# DAC_Block.net
KiCad netlist of a schematic drawn in Altium Designer
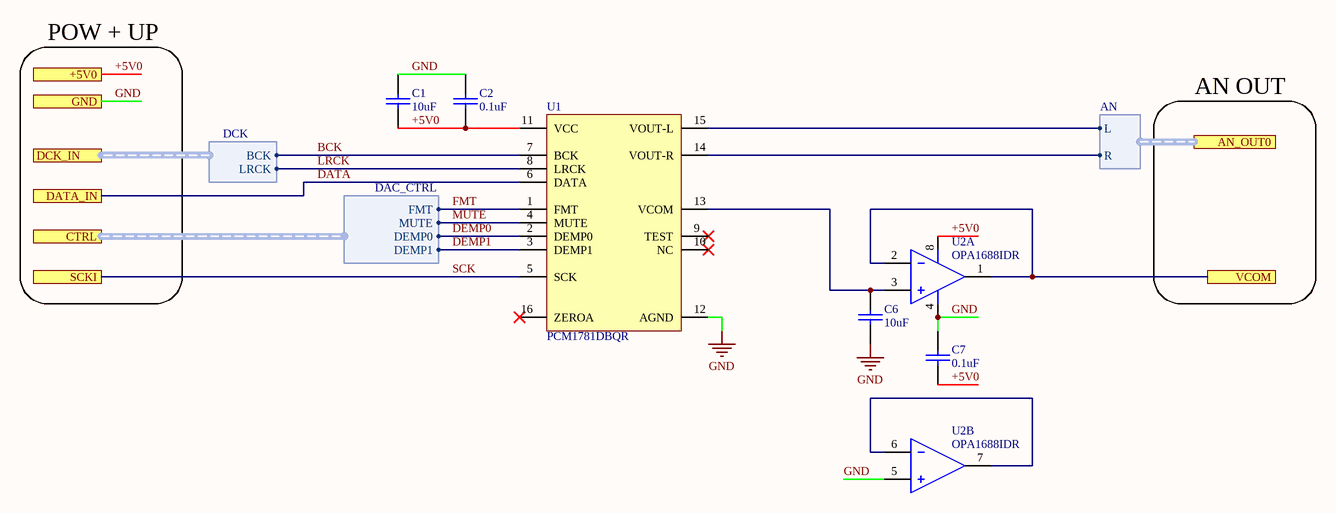
[diagram p0: DAC_Block.SchDoc]

(export (version "E")
  (design (tool "Eeschema 10.0.6"))
  (components
    (comp (ref "C1")
      (value "10uF")
      (footprint "0603-CAP-TDK")
      (fields (field (name "JLCPART") "C96446"))
      (libsource (lib "LIB2022 - Passives") (part "CAP-SMD"))
    )
    (comp (ref "C2")
      (value "0.1uF")
      (footprint "0402-CAP-TDK")
      (fields (field (name "JLCPART") "C307331"))
      (libsource (lib "LIB2022 - Passives") (part "CAP-SMD"))
    )
    (comp (ref "C6")
      (value "10uF")
      (footprint "0603-CAP-TDK")
      (fields (field (name "JLCPART") "C96446"))
      (libsource (lib "LIB2022 - Passives") (part "CAP-SMD"))
    )
    (comp (ref "C7")
      (value "0.1uF")
      (footprint "0402-CAP-TDK")
      (fields (field (name "JLCPART") "C307331"))
      (libsource (lib "LIB2022 - Passives") (part "CAP-SMD"))
    )
    (comp (ref "U1")
      (value "PCM1781DBQR")
      (footprint "TI-SSOP-16 - DBQ0016A")
      (description "DAC, Audio 24 b 192k DSP, I2S 16-SSOP")
      (fields (field (name "JLCPART") "C2667281"))
      (libsource (lib "LIB2022 - ICs") (part "PCM1781DBQR"))
    )
    (comp (ref "U2")
      (value "OPA1688IDR")
      (footprint "TI-SOIC-8")
      (description "Rail-To-Rail Amplifier 2 Circuit - 8-SOIC")
      (fields (field (name "JLCPART") "C206212"))
      (libsource (lib "LIB2022 - ICs") (part "OPA1688IDR"))
    )
  )
  (nets
    (net (code "4") (name "/+5V0") (class "Default")
      (node (ref "C1") (pin "2") (pinfunction "2_2") (pintype "passive"))
      (node (ref "C2") (pin "2") (pinfunction "2_2") (pintype "passive"))
      (node (ref "C7") (pin "1") (pinfunction "1_1") (pintype "passive"))
      (node (ref "U1") (pin "11") (pinfunction "VCC_11") (pintype "passive"))
      (node (ref "U2") (pin "8") (pinfunction "VDD_8") (pintype "power_in"))
    )
    (net (code "5") (name "/BCK") (class "Default")
      (node (ref "U1") (pin "7") (pinfunction "BCK_7") (pintype "passive"))
    )
    (net (code "6") (name "/DATA") (class "Default")
      (node (ref "U1") (pin "6") (pinfunction "DATA_6") (pintype "passive"))
    )
    (net (code "7") (name "/DEMP0") (class "Default")
      (node (ref "U1") (pin "2") (pinfunction "DEMP0_2") (pintype "passive"))
    )
    (net (code "8") (name "/DEMP1") (class "Default")
      (node (ref "U1") (pin "3") (pinfunction "DEMP1_3") (pintype "passive"))
    )
    (net (code "9") (name "/FMT") (class "Default")
      (node (ref "U1") (pin "1") (pinfunction "FMT_1") (pintype "passive"))
    )
    (net (code "10") (name "/L") (class "Default")
      (node (ref "U1") (pin "15") (pinfunction "VOUT-L_15") (pintype "passive"))
    )
    (net (code "11") (name "/LRCK") (class "Default")
      (node (ref "U1") (pin "8") (pinfunction "LRCK_8") (pintype "passive"))
    )
    (net (code "12") (name "/MUTE") (class "Default")
      (node (ref "U1") (pin "4") (pinfunction "MUTE_4") (pintype "passive"))
    )
    (net (code "13") (name "/R") (class "Default")
      (node (ref "U1") (pin "14") (pinfunction "VOUT-R_14") (pintype "passive"))
    )
    (net (code "14") (name "/SCK") (class "Default")
      (node (ref "U1") (pin "5") (pinfunction "SCK_5") (pintype "passive"))
    )
    (net (code "15") (name "/VCOM") (class "Default")
      (node (ref "U2") (pin "1") (pinfunction "1OUT_1") (pintype "passive"))
      (node (ref "U2") (pin "2") (pinfunction "1IN-_2") (pintype "passive"))
    )
    (net (code "19") (name "GND") (class "Default")
      (node (ref "C1") (pin "1") (pinfunction "1_1") (pintype "passive"))
      (node (ref "C2") (pin "1") (pinfunction "1_1") (pintype "passive"))
      (node (ref "C6") (pin "1") (pinfunction "1_1") (pintype "passive"))
      (node (ref "C7") (pin "2") (pinfunction "2_2") (pintype "passive"))
      (node (ref "U1") (pin "12") (pinfunction "AGND_12") (pintype "passive"))
      (node (ref "U2") (pin "4") (pinfunction "GND_4") (pintype "passive"))
      (node (ref "U2") (pin "5") (pinfunction "2IN+_5") (pintype "passive"))
    )
    (net (code "20") (name "Net-(U1-VCOM)") (class "Default")
      (node (ref "C6") (pin "2") (pinfunction "2_2") (pintype "passive"))
      (node (ref "U1") (pin "13") (pinfunction "VCOM_13") (pintype "passive"))
      (node (ref "U2") (pin "3") (pinfunction "1IN+_3") (pintype "passive"))
    )
    (net (code "21") (name "Net-(U2B-2IN-)") (class "Default")
      (node (ref "U2") (pin "6") (pinfunction "2IN-_6") (pintype "passive"))
      (node (ref "U2") (pin "7") (pinfunction "2OUT_7") (pintype "passive"))
    )
    (net (code "22") (name "unconnected-(U1-NC-Pad10)") (class "Default")
      (node (ref "U1") (pin "10") (pinfunction "NC_10") (pintype "passive+no_connect"))
    )
    (net (code "23") (name "unconnected-(U1-TEST-Pad9)") (class "Default")
      (node (ref "U1") (pin "9") (pinfunction "TEST_9") (pintype "passive+no_connect"))
    )
    (net (code "24") (name "unconnected-(U1-ZEROA-Pad16)") (class "Default")
      (node (ref "U1") (pin "16") (pinfunction "ZEROA_16") (pintype "passive+no_connect"))
    )
  )
)
